# driver4-8.net
KiCad netlist of a schematic drawn in Altium Designer
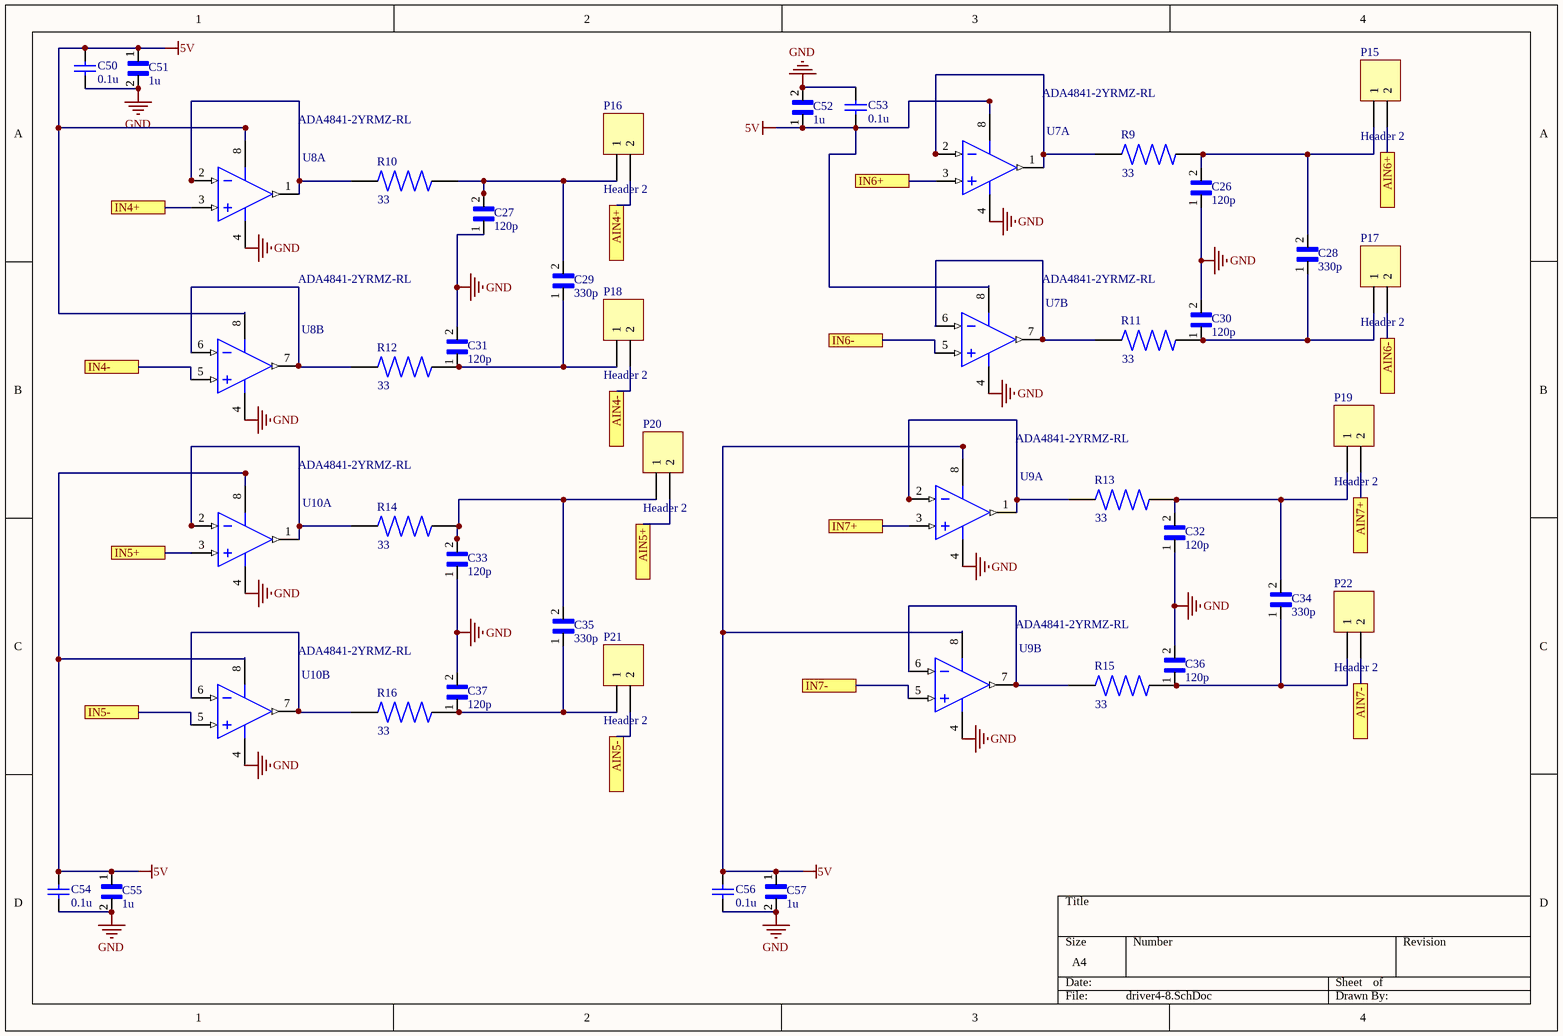
[diagram p0: driver4-8.SchDoc]

(export (version "E")
  (design (tool "Eeschema 10.0.6"))
  (components
    (comp (ref "C26")
      (value "120p")
      (footprint "12061A121JAT2A:CAPC3216X94N")
      (description "CERAMIC CAPACITOR 120PF 100V, C0G, 5%, 1206")
      (fields (field (name "MF") "{'manufacturer': u'AVX'}") (field (name "MP") "12061A121JAT2A"))
      (libsource (lib "12061A121JAT2A") (part "12061A121JAT2A"))
    )
    (comp (ref "C27")
      (value "120p")
      (footprint "12061A121JAT2A:CAPC3216X94N")
      (description "CERAMIC CAPACITOR 120PF 100V, C0G, 5%, 1206")
      (fields (field (name "MF") "{'manufacturer': u'AVX'}") (field (name "MP") "12061A121JAT2A"))
      (libsource (lib "12061A121JAT2A") (part "12061A121JAT2A"))
    )
    (comp (ref "C28")
      (value "330p")
      (footprint "12065A331JAT2A:CAPC3216X94N")
      (fields (field (name "MF") "{'manufacturer': u'AVX'}") (field (name "MP") "12065A331JAT2A"))
      (libsource (lib "12065A331JAT2A") (part "12065A331JAT2A"))
    )
    (comp (ref "C29")
      (value "330p")
      (footprint "12065A331JAT2A:CAPC3216X94N")
      (fields (field (name "MF") "{'manufacturer': u'AVX'}") (field (name "MP") "12065A331JAT2A"))
      (libsource (lib "12065A331JAT2A") (part "12065A331JAT2A"))
    )
    (comp (ref "C30")
      (value "120p")
      (footprint "12061A121JAT2A:CAPC3216X94N")
      (description "CERAMIC CAPACITOR 120PF 100V, C0G, 5%, 1206")
      (fields (field (name "MF") "{'manufacturer': u'AVX'}") (field (name "MP") "12061A121JAT2A"))
      (libsource (lib "12061A121JAT2A") (part "12061A121JAT2A"))
    )
    (comp (ref "C31")
      (value "120p")
      (footprint "12061A121JAT2A:CAPC3216X94N")
      (description "CERAMIC CAPACITOR 120PF 100V, C0G, 5%, 1206")
      (fields (field (name "MF") "{'manufacturer': u'AVX'}") (field (name "MP") "12061A121JAT2A"))
      (libsource (lib "12061A121JAT2A") (part "12061A121JAT2A"))
    )
    (comp (ref "C32")
      (value "120p")
      (footprint "12061A121JAT2A:CAPC3216X94N")
      (description "CERAMIC CAPACITOR 120PF 100V, C0G, 5%, 1206")
      (fields (field (name "MF") "{'manufacturer': u'AVX'}") (field (name "MP") "12061A121JAT2A"))
      (libsource (lib "12061A121JAT2A") (part "12061A121JAT2A"))
    )
    (comp (ref "C33")
      (value "120p")
      (footprint "12061A121JAT2A:CAPC3216X94N")
      (description "CERAMIC CAPACITOR 120PF 100V, C0G, 5%, 1206")
      (fields (field (name "MF") "{'manufacturer': u'AVX'}") (field (name "MP") "12061A121JAT2A"))
      (libsource (lib "12061A121JAT2A") (part "12061A121JAT2A"))
    )
    (comp (ref "C34")
      (value "330p")
      (footprint "12065A331JAT2A:CAPC3216X94N")
      (fields (field (name "MF") "{'manufacturer': u'AVX'}") (field (name "MP") "12065A331JAT2A"))
      (libsource (lib "12065A331JAT2A") (part "12065A331JAT2A"))
    )
    (comp (ref "C35")
      (value "330p")
      (footprint "12065A331JAT2A:CAPC3216X94N")
      (fields (field (name "MF") "{'manufacturer': u'AVX'}") (field (name "MP") "12065A331JAT2A"))
      (libsource (lib "12065A331JAT2A") (part "12065A331JAT2A"))
    )
    (comp (ref "C36")
      (value "120p")
      (footprint "12061A121JAT2A:CAPC3216X94N")
      (description "CERAMIC CAPACITOR 120PF 100V, C0G, 5%, 1206")
      (fields (field (name "MF") "{'manufacturer': u'AVX'}") (field (name "MP") "12061A121JAT2A"))
      (libsource (lib "12061A121JAT2A") (part "12061A121JAT2A"))
    )
    (comp (ref "C37")
      (value "120p")
      (footprint "12061A121JAT2A:CAPC3216X94N")
      (description "CERAMIC CAPACITOR 120PF 100V, C0G, 5%, 1206")
      (fields (field (name "MF") "{'manufacturer': u'AVX'}") (field (name "MP") "12061A121JAT2A"))
      (libsource (lib "12061A121JAT2A") (part "12061A121JAT2A"))
    )
    (comp (ref "C50")
      (value "0.1u")
      (footprint "CAPC3216X94X50ML20T25")
      (description "Chip Capacitor, Ceramic, 100 nF, 10%, 50 V, 1206, RoHS, Tape and Reel")
      (fields (field (name "MANUFACTURER") "AVX"))
      (libsource (lib "Altium Content Vault") (part "CAP-NP-2"))
    )
    (comp (ref "C51")
      (value "1u")
      (footprint "1206YC105KAT2A:CAPC3216X127N")
      (description "Cap Ceramic 1uF 16V X7R 10% SMD 1206 125ÂÂŽ T/R")
      (fields (field (name "MF") "{'manufacturer': u'AVX'}") (field (name "MP") "1206YC105KAT2A"))
      (libsource (lib "1206YC105KAT2A") (part "1206YC105KAT2A"))
    )
    (comp (ref "C52")
      (value "1u")
      (footprint "1206YC105KAT2A:CAPC3216X127N")
      (description "Cap Ceramic 1uF 16V X7R 10% SMD 1206 125ÂÂŽ T/R")
      (fields (field (name "MF") "{'manufacturer': u'AVX'}") (field (name "MP") "1206YC105KAT2A"))
      (libsource (lib "") (part "1206YC105KAT2A_1"))
    )
    (comp (ref "C53")
      (value "0.1u")
      (footprint "CAPC3216X94X50ML20T25")
      (description "Chip Capacitor, Ceramic, 100 nF, 10%, 50 V, 1206, RoHS, Tape and Reel")
      (fields (field (name "MANUFACTURER") "AVX"))
      (libsource (lib "Altium Content Vault") (part "CAP-NP-2"))
    )
    (comp (ref "C54")
      (value "0.1u")
      (footprint "CAPC3216X94X50ML20T25")
      (description "Chip Capacitor, Ceramic, 100 nF, 10%, 50 V, 1206, RoHS, Tape and Reel")
      (fields (field (name "MANUFACTURER") "AVX"))
      (libsource (lib "Altium Content Vault") (part "CAP-NP-2"))
    )
    (comp (ref "C55")
      (value "1u")
      (footprint "1206YC105KAT2A:CAPC3216X127N")
      (description "Cap Ceramic 1uF 16V X7R 10% SMD 1206 125ÂÂŽ T/R")
      (fields (field (name "MF") "{'manufacturer': u'AVX'}") (field (name "MP") "1206YC105KAT2A"))
      (libsource (lib "1206YC105KAT2A") (part "1206YC105KAT2A"))
    )
    (comp (ref "C56")
      (value "0.1u")
      (footprint "CAPC3216X94X50ML20T25")
      (description "Chip Capacitor, Ceramic, 100 nF, 10%, 50 V, 1206, RoHS, Tape and Reel")
      (fields (field (name "MANUFACTURER") "AVX"))
      (libsource (lib "Altium Content Vault") (part "CAP-NP-2"))
    )
    (comp (ref "C57")
      (value "1u")
      (footprint "1206YC105KAT2A:CAPC3216X127N")
      (description "Cap Ceramic 1uF 16V X7R 10% SMD 1206 125ÂÂŽ T/R")
      (fields (field (name "MF") "{'manufacturer': u'AVX'}") (field (name "MP") "1206YC105KAT2A"))
      (libsource (lib "1206YC105KAT2A") (part "1206YC105KAT2A"))
    )
    (comp (ref "P15")
      (value "Header 2")
      (footprint "HDR1X2")
      (description "Header, 2-Pin")
      (fields (field (name "PUBLISHER") "Altium Limited"))
      (libsource (lib "Miscellaneous Connectors") (part "Header 2"))
    )
    (comp (ref "P16")
      (value "Header 2")
      (footprint "HDR1X2")
      (description "Header, 2-Pin")
      (fields (field (name "PUBLISHER") "Altium Limited"))
      (libsource (lib "Miscellaneous Connectors") (part "Header 2"))
    )
    (comp (ref "P17")
      (value "Header 2")
      (footprint "HDR1X2")
      (description "Header, 2-Pin")
      (fields (field (name "PUBLISHER") "Altium Limited"))
      (libsource (lib "Miscellaneous Connectors") (part "Header 2"))
    )
    (comp (ref "P18")
      (value "Header 2")
      (footprint "HDR1X2")
      (description "Header, 2-Pin")
      (fields (field (name "PUBLISHER") "Altium Limited"))
      (libsource (lib "Miscellaneous Connectors") (part "Header 2"))
    )
    (comp (ref "P19")
      (value "Header 2")
      (footprint "HDR1X2")
      (description "Header, 2-Pin")
      (fields (field (name "PUBLISHER") "Altium Limited"))
      (libsource (lib "Miscellaneous Connectors") (part "Header 2"))
    )
    (comp (ref "P20")
      (value "Header 2")
      (footprint "HDR1X2")
      (description "Header, 2-Pin")
      (fields (field (name "PUBLISHER") "Altium Limited"))
      (libsource (lib "Miscellaneous Connectors") (part "Header 2"))
    )
    (comp (ref "P21")
      (value "Header 2")
      (footprint "HDR1X2")
      (description "Header, 2-Pin")
      (fields (field (name "PUBLISHER") "Altium Limited"))
      (libsource (lib "Miscellaneous Connectors") (part "Header 2"))
    )
    (comp (ref "P22")
      (value "Header 2")
      (footprint "HDR1X2")
      (description "Header, 2-Pin")
      (fields (field (name "PUBLISHER") "Altium Limited"))
      (libsource (lib "Miscellaneous Connectors") (part "Header 2"))
    )
    (comp (ref "R9")
      (value "33")
      (footprint "RTAN1206BKE33R0:RESC3116X75N")
      (fields
        (field (name "MF") "{'manufacturer': u'Stackpole Electronics Inc'}")
        (field (name "MP") "RTAN1206BKE33R0")
      )
      (libsource (lib "RTAN1206BKE33R0") (part "RTAN1206BKE33R0"))
    )
    (comp (ref "R10")
      (value "33")
      (footprint "RTAN1206BKE33R0:RESC3116X75N")
      (fields
        (field (name "MF") "{'manufacturer': u'Stackpole Electronics Inc'}")
        (field (name "MP") "RTAN1206BKE33R0")
      )
      (libsource (lib "RTAN1206BKE33R0") (part "RTAN1206BKE33R0"))
    )
    (comp (ref "R11")
      (value "33")
      (footprint "RTAN1206BKE33R0:RESC3116X75N")
      (fields
        (field (name "MF") "{'manufacturer': u'Stackpole Electronics Inc'}")
        (field (name "MP") "RTAN1206BKE33R0")
      )
      (libsource (lib "RTAN1206BKE33R0") (part "RTAN1206BKE33R0"))
    )
    (comp (ref "R12")
      (value "33")
      (footprint "RTAN1206BKE33R0:RESC3116X75N")
      (fields
        (field (name "MF") "{'manufacturer': u'Stackpole Electronics Inc'}")
        (field (name "MP") "RTAN1206BKE33R0")
      )
      (libsource (lib "RTAN1206BKE33R0") (part "RTAN1206BKE33R0"))
    )
    (comp (ref "R13")
      (value "33")
      (footprint "RTAN1206BKE33R0:RESC3116X75N")
      (fields
        (field (name "MF") "{'manufacturer': u'Stackpole Electronics Inc'}")
        (field (name "MP") "RTAN1206BKE33R0")
      )
      (libsource (lib "RTAN1206BKE33R0") (part "RTAN1206BKE33R0"))
    )
    (comp (ref "R14")
      (value "33")
      (footprint "RTAN1206BKE33R0:RESC3116X75N")
      (fields
        (field (name "MF") "{'manufacturer': u'Stackpole Electronics Inc'}")
        (field (name "MP") "RTAN1206BKE33R0")
      )
      (libsource (lib "RTAN1206BKE33R0") (part "RTAN1206BKE33R0"))
    )
    (comp (ref "R15")
      (value "33")
      (footprint "RTAN1206BKE33R0:RESC3116X75N")
      (fields
        (field (name "MF") "{'manufacturer': u'Stackpole Electronics Inc'}")
        (field (name "MP") "RTAN1206BKE33R0")
      )
      (libsource (lib "RTAN1206BKE33R0") (part "RTAN1206BKE33R0"))
    )
    (comp (ref "R16")
      (value "33")
      (footprint "RTAN1206BKE33R0:RESC3116X75N")
      (fields
        (field (name "MF") "{'manufacturer': u'Stackpole Electronics Inc'}")
        (field (name "MP") "RTAN1206BKE33R0")
      )
      (libsource (lib "RTAN1206BKE33R0") (part "RTAN1206BKE33R0"))
    )
    (comp (ref "U7")
      (value "ADA4841-2YRMZ-RL")
      (footprint "ADI-RM-8_M")
      (fields (field (name "MANUFACTURER") "Analog Devices") (field (name "GENERIC PART NUMBER") "ADA4841-2"))
      (libsource (lib "Altium Content Vault") (part "ADI-AD8XXX_823_A48X1-X-8"))
    )
    (comp (ref "U8")
      (value "ADA4841-2YRMZ-RL")
      (footprint "ADI-RM-8_M")
      (fields (field (name "MANUFACTURER") "Analog Devices") (field (name "GENERIC PART NUMBER") "ADA4841-2"))
      (libsource (lib "Altium Content Vault") (part "ADI-AD8XXX_823_A48X1-X-8"))
    )
    (comp (ref "U9")
      (value "ADA4841-2YRMZ-RL")
      (footprint "ADI-RM-8_M")
      (fields (field (name "MANUFACTURER") "Analog Devices") (field (name "GENERIC PART NUMBER") "ADA4841-2"))
      (libsource (lib "Altium Content Vault") (part "ADI-AD8XXX_823_A48X1-X-8"))
    )
    (comp (ref "U10")
      (value "ADA4841-2YRMZ-RL")
      (footprint "ADI-RM-8_M")
      (fields (field (name "MANUFACTURER") "Analog Devices") (field (name "GENERIC PART NUMBER") "ADA4841-2"))
      (libsource (lib "Altium Content Vault") (part "ADI-AD8XXX_823_A48X1-X-8"))
    )
  )
  (nets
    (net (code "1") (name "/AIN4+") (class "Default")
      (node (ref "P16") (pin "2") (pinfunction "2_2") (pintype "passive"))
    )
    (net (code "2") (name "/AIN4-") (class "Default")
      (node (ref "P18") (pin "2") (pinfunction "2_2") (pintype "passive"))
    )
    (net (code "3") (name "/AIN5+") (class "Default")
      (node (ref "P20") (pin "2") (pinfunction "2_2") (pintype "passive"))
    )
    (net (code "4") (name "/AIN5-") (class "Default")
      (node (ref "P21") (pin "2") (pinfunction "2_2") (pintype "passive"))
    )
    (net (code "5") (name "/AIN6+") (class "Default")
      (node (ref "P15") (pin "2") (pinfunction "2_2") (pintype "passive"))
    )
    (net (code "6") (name "/AIN6-") (class "Default")
      (node (ref "P17") (pin "2") (pinfunction "2_2") (pintype "passive"))
    )
    (net (code "7") (name "/AIN7+") (class "Default")
      (node (ref "P19") (pin "2") (pinfunction "2_2") (pintype "passive"))
    )
    (net (code "8") (name "/AIN7-") (class "Default")
      (node (ref "P22") (pin "2") (pinfunction "2_2") (pintype "passive"))
    )
    (net (code "9") (name "/IN4+") (class "Default")
      (node (ref "U8") (pin "3") (pinfunction "+IN_1_3") (pintype "input"))
    )
    (net (code "10") (name "/IN4-") (class "Default")
      (node (ref "U8") (pin "5") (pinfunction "+IN_2_5") (pintype "input"))
    )
    (net (code "11") (name "/IN5+") (class "Default")
      (node (ref "U10") (pin "3") (pinfunction "+IN_1_3") (pintype "input"))
    )
    (net (code "12") (name "/IN5-") (class "Default")
      (node (ref "U10") (pin "5") (pinfunction "+IN_2_5") (pintype "input"))
    )
    (net (code "13") (name "/IN6+") (class "Default")
      (node (ref "U7") (pin "3") (pinfunction "+IN_1_3") (pintype "input"))
    )
    (net (code "14") (name "/IN6-") (class "Default")
      (node (ref "U7") (pin "5") (pinfunction "+IN_2_5") (pintype "input"))
    )
    (net (code "15") (name "/IN7+") (class "Default")
      (node (ref "U9") (pin "3") (pinfunction "+IN_1_3") (pintype "input"))
    )
    (net (code "16") (name "/IN7-") (class "Default")
      (node (ref "U9") (pin "5") (pinfunction "+IN_2_5") (pintype "input"))
    )
    (net (code "17") (name "5V") (class "Default")
      (node (ref "C50") (pin "1") (pinfunction "1_1") (pintype "passive"))
      (node (ref "C51") (pin "1") (pinfunction "1_1") (pintype "passive"))
      (node (ref "C52") (pin "1") (pinfunction "1_1") (pintype "passive"))
      (node (ref "C53") (pin "1") (pinfunction "1_1") (pintype "passive"))
      (node (ref "C54") (pin "1") (pinfunction "1_1") (pintype "passive"))
      (node (ref "C55") (pin "1") (pinfunction "1_1") (pintype "passive"))
      (node (ref "C56") (pin "1") (pinfunction "1_1") (pintype "passive"))
      (node (ref "C57") (pin "1") (pinfunction "1_1") (pintype "passive"))
      (node (ref "U10") (pin "8") (pinfunction "+VS_8") (pintype "power_in"))
      (node (ref "U7") (pin "8") (pinfunction "+VS_8") (pintype "power_in"))
      (node (ref "U8") (pin "8") (pinfunction "+VS_8") (pintype "power_in"))
      (node (ref "U9") (pin "8") (pinfunction "+VS_8") (pintype "power_in"))
    )
    (net (code "18") (name "GND") (class "Default")
      (node (ref "C26") (pin "1") (pinfunction "1_1") (pintype "passive"))
      (node (ref "C27") (pin "1") (pinfunction "1_1") (pintype "passive"))
      (node (ref "C30") (pin "2") (pinfunction "2_2") (pintype "passive"))
      (node (ref "C31") (pin "2") (pinfunction "2_2") (pintype "passive"))
      (node (ref "C32") (pin "1") (pinfunction "1_1") (pintype "passive"))
      (node (ref "C33") (pin "1") (pinfunction "1_1") (pintype "passive"))
      (node (ref "C36") (pin "2") (pinfunction "2_2") (pintype "passive"))
      (node (ref "C37") (pin "2") (pinfunction "2_2") (pintype "passive"))
      (node (ref "C50") (pin "2") (pinfunction "2_2") (pintype "passive"))
      (node (ref "C51") (pin "2") (pinfunction "2_2") (pintype "passive"))
      (node (ref "C52") (pin "2") (pinfunction "2_2") (pintype "passive"))
      (node (ref "C53") (pin "2") (pinfunction "2_2") (pintype "passive"))
      (node (ref "C54") (pin "2") (pinfunction "2_2") (pintype "passive"))
      (node (ref "C55") (pin "2") (pinfunction "2_2") (pintype "passive"))
      (node (ref "C56") (pin "2") (pinfunction "2_2") (pintype "passive"))
      (node (ref "C57") (pin "2") (pinfunction "2_2") (pintype "passive"))
      (node (ref "U10") (pin "4") (pinfunction "-VS_4") (pintype "power_in"))
      (node (ref "U7") (pin "4") (pinfunction "-VS_4") (pintype "power_in"))
      (node (ref "U8") (pin "4") (pinfunction "-VS_4") (pintype "power_in"))
      (node (ref "U9") (pin "4") (pinfunction "-VS_4") (pintype "power_in"))
    )
    (net (code "19") (name "Net-(C26-Pad2)") (class "Default")
      (node (ref "C26") (pin "2") (pinfunction "2_2") (pintype "passive"))
      (node (ref "C28") (pin "2") (pinfunction "2_2") (pintype "passive"))
      (node (ref "P15") (pin "1") (pinfunction "1_1") (pintype "passive"))
      (node (ref "R9") (pin "2") (pinfunction "2_2") (pintype "passive"))
    )
    (net (code "20") (name "Net-(C27-Pad2)") (class "Default")
      (node (ref "C27") (pin "2") (pinfunction "2_2") (pintype "passive"))
      (node (ref "C29") (pin "2") (pinfunction "2_2") (pintype "passive"))
      (node (ref "P16") (pin "1") (pinfunction "1_1") (pintype "passive"))
      (node (ref "R10") (pin "2") (pinfunction "2_2") (pintype "passive"))
    )
    (net (code "21") (name "Net-(C28-Pad1)") (class "Default")
      (node (ref "C28") (pin "1") (pinfunction "1_1") (pintype "passive"))
      (node (ref "C30") (pin "1") (pinfunction "1_1") (pintype "passive"))
      (node (ref "P17") (pin "1") (pinfunction "1_1") (pintype "passive"))
      (node (ref "R11") (pin "2") (pinfunction "2_2") (pintype "passive"))
    )
    (net (code "22") (name "Net-(C29-Pad1)") (class "Default")
      (node (ref "C29") (pin "1") (pinfunction "1_1") (pintype "passive"))
      (node (ref "C31") (pin "1") (pinfunction "1_1") (pintype "passive"))
      (node (ref "P18") (pin "1") (pinfunction "1_1") (pintype "passive"))
      (node (ref "R12") (pin "2") (pinfunction "2_2") (pintype "passive"))
    )
    (net (code "23") (name "Net-(C32-Pad2)") (class "Default")
      (node (ref "C32") (pin "2") (pinfunction "2_2") (pintype "passive"))
      (node (ref "C34") (pin "2") (pinfunction "2_2") (pintype "passive"))
      (node (ref "P19") (pin "1") (pinfunction "1_1") (pintype "passive"))
      (node (ref "R13") (pin "2") (pinfunction "2_2") (pintype "passive"))
    )
    (net (code "24") (name "Net-(C33-Pad2)") (class "Default")
      (node (ref "C33") (pin "2") (pinfunction "2_2") (pintype "passive"))
      (node (ref "C35") (pin "2") (pinfunction "2_2") (pintype "passive"))
      (node (ref "P20") (pin "1") (pinfunction "1_1") (pintype "passive"))
      (node (ref "R14") (pin "2") (pinfunction "2_2") (pintype "passive"))
    )
    (net (code "25") (name "Net-(C34-Pad1)") (class "Default")
      (node (ref "C34") (pin "1") (pinfunction "1_1") (pintype "passive"))
      (node (ref "C36") (pin "1") (pinfunction "1_1") (pintype "passive"))
      (node (ref "P22") (pin "1") (pinfunction "1_1") (pintype "passive"))
      (node (ref "R15") (pin "2") (pinfunction "2_2") (pintype "passive"))
    )
    (net (code "26") (name "Net-(C35-Pad1)") (class "Default")
      (node (ref "C35") (pin "1") (pinfunction "1_1") (pintype "passive"))
      (node (ref "C37") (pin "1") (pinfunction "1_1") (pintype "passive"))
      (node (ref "P21") (pin "1") (pinfunction "1_1") (pintype "passive"))
      (node (ref "R16") (pin "2") (pinfunction "2_2") (pintype "passive"))
    )
    (net (code "27") (name "Net-(U7A--IN_1)") (class "Default")
      (node (ref "R9") (pin "1") (pinfunction "1_1") (pintype "passive"))
      (node (ref "U7") (pin "1") (pinfunction "OUT_1_1") (pintype "output"))
      (node (ref "U7") (pin "2") (pinfunction "-IN_1_2") (pintype "input"))
    )
    (net (code "28") (name "Net-(U7B--IN_2)") (class "Default")
      (node (ref "R11") (pin "1") (pinfunction "1_1") (pintype "passive"))
      (node (ref "U7") (pin "6") (pinfunction "-IN_2_6") (pintype "input"))
      (node (ref "U7") (pin "7") (pinfunction "OUT_2_7") (pintype "output"))
    )
    (net (code "29") (name "Net-(U8A--IN_1)") (class "Default")
      (node (ref "R10") (pin "1") (pinfunction "1_1") (pintype "passive"))
      (node (ref "U8") (pin "1") (pinfunction "OUT_1_1") (pintype "output"))
      (node (ref "U8") (pin "2") (pinfunction "-IN_1_2") (pintype "input"))
    )
    (net (code "30") (name "Net-(U8B--IN_2)") (class "Default")
      (node (ref "R12") (pin "1") (pinfunction "1_1") (pintype "passive"))
      (node (ref "U8") (pin "6") (pinfunction "-IN_2_6") (pintype "input"))
      (node (ref "U8") (pin "7") (pinfunction "OUT_2_7") (pintype "output"))
    )
    (net (code "31") (name "Net-(U9A--IN_1)") (class "Default")
      (node (ref "R13") (pin "1") (pinfunction "1_1") (pintype "passive"))
      (node (ref "U9") (pin "1") (pinfunction "OUT_1_1") (pintype "output"))
      (node (ref "U9") (pin "2") (pinfunction "-IN_1_2") (pintype "input"))
    )
    (net (code "32") (name "Net-(U9B--IN_2)") (class "Default")
      (node (ref "R15") (pin "1") (pinfunction "1_1") (pintype "passive"))
      (node (ref "U9") (pin "6") (pinfunction "-IN_2_6") (pintype "input"))
      (node (ref "U9") (pin "7") (pinfunction "OUT_2_7") (pintype "output"))
    )
    (net (code "33") (name "Net-(U10A--IN_1)") (class "Default")
      (node (ref "R14") (pin "1") (pinfunction "1_1") (pintype "passive"))
      (node (ref "U10") (pin "1") (pinfunction "OUT_1_1") (pintype "output"))
      (node (ref "U10") (pin "2") (pinfunction "-IN_1_2") (pintype "input"))
    )
    (net (code "34") (name "Net-(U10B--IN_2)") (class "Default")
      (node (ref "R16") (pin "1") (pinfunction "1_1") (pintype "passive"))
      (node (ref "U10") (pin "6") (pinfunction "-IN_2_6") (pintype "input"))
      (node (ref "U10") (pin "7") (pinfunction "OUT_2_7") (pintype "output"))
    )
  )
)
